# cyrf6936-bob.net
KiCad netlist of a schematic drawn in EAGLE
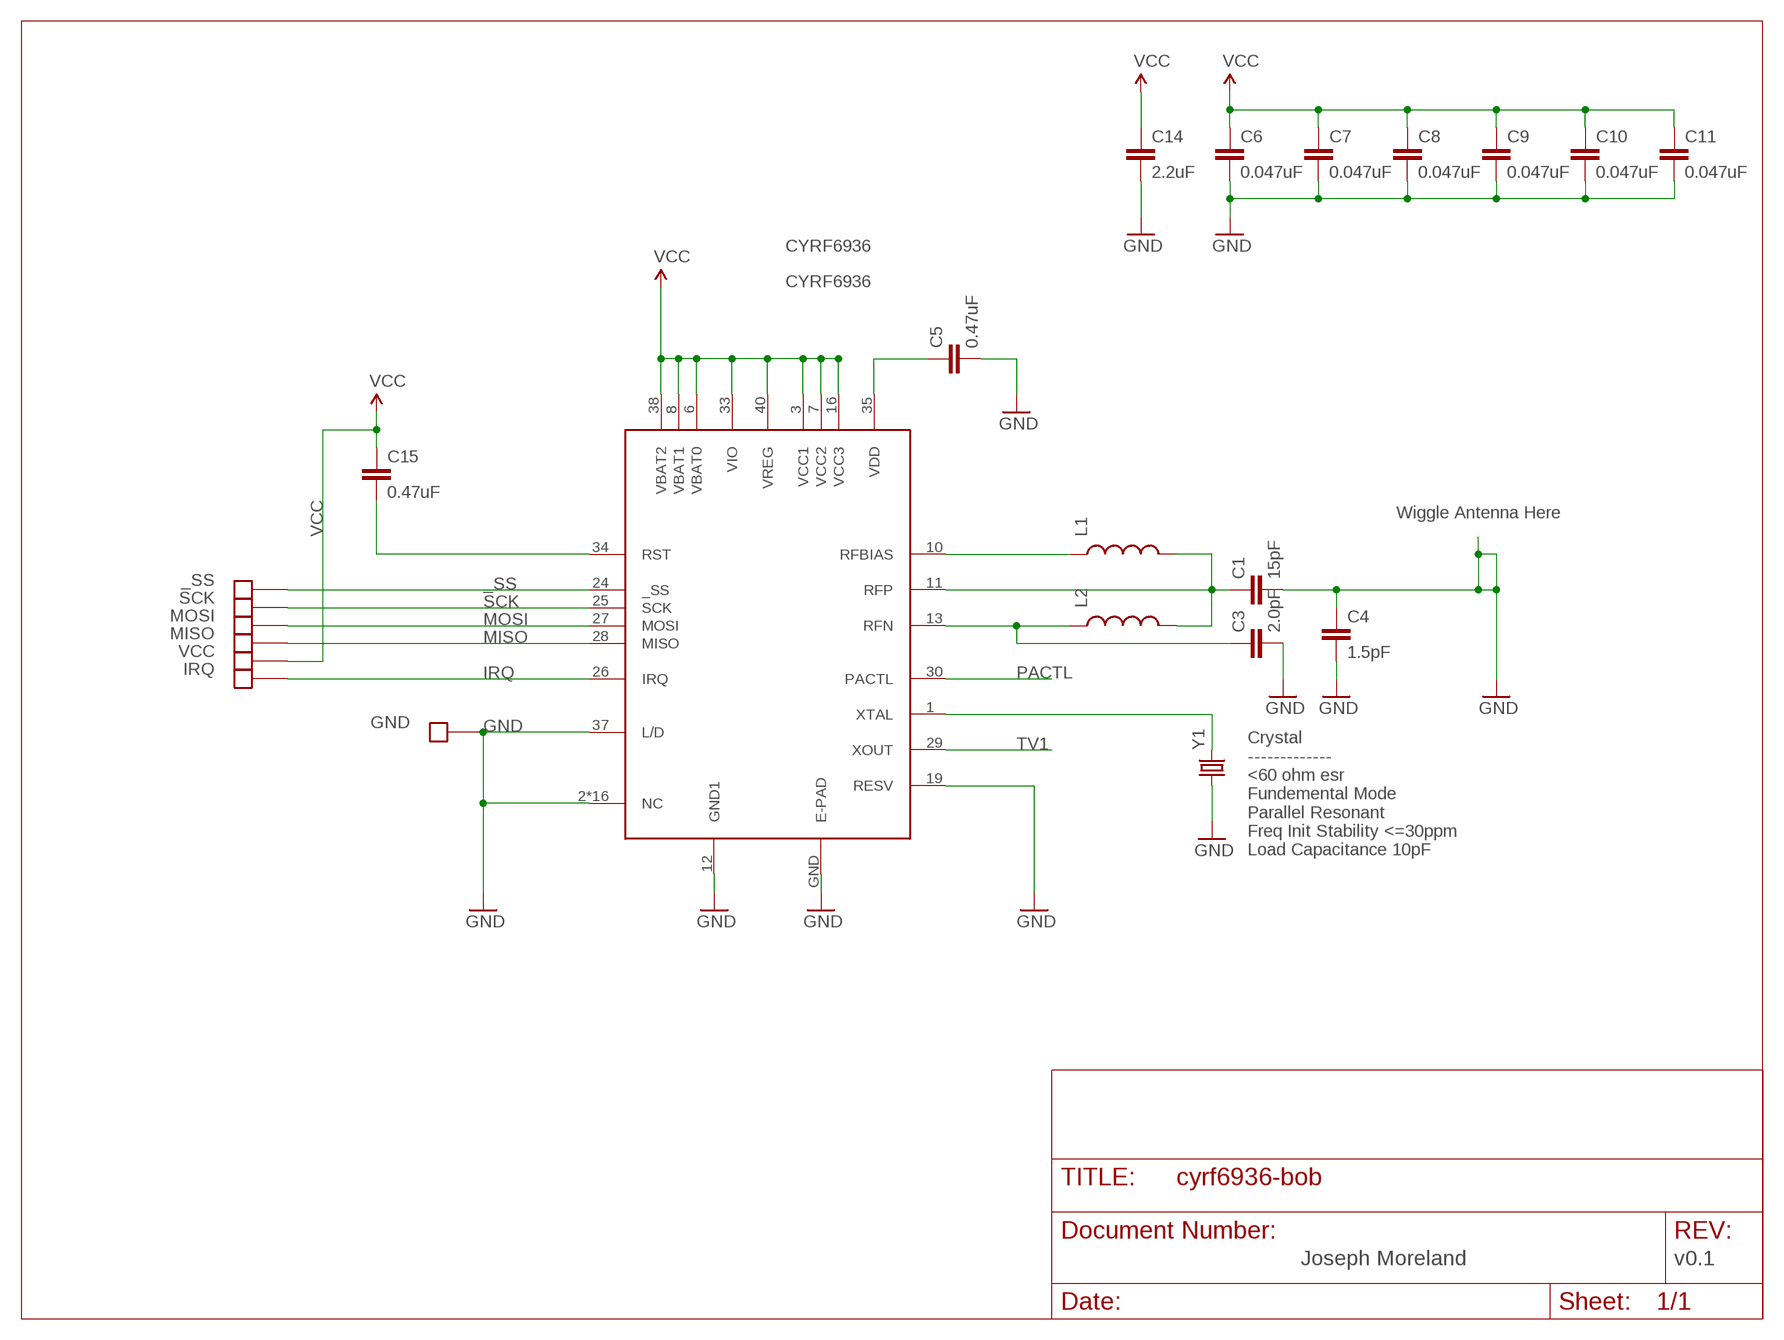
[diagram p0: schematic, sheet 1]

(export (version "E")
  (design (tool "Eeschema 10.0.6"))
  (components
    (comp (ref "C1")
      (value "15pF")
      (footprint "eagle-import:0402-CAP")
      (fields (field (name "PARTNO") "C0402C150J5GACTU"))
      (libsource (lib "eagle-import") (part "CAP0402-CAP"))
    )
    (comp (ref "C3")
      (value "2.0pF")
      (footprint "eagle-import:0402-CAP")
      (fields (field (name "PARTNO") "C0402C209C5GACTU"))
      (libsource (lib "eagle-import") (part "CAP0402-CAP"))
    )
    (comp (ref "C4")
      (value "1.5pF")
      (footprint "eagle-import:0402-CAP")
      (fields (field (name "PARTNO") "C0402C159B5GACTU"))
      (libsource (lib "eagle-import") (part "CAP0402-CAP"))
    )
    (comp (ref "C5")
      (value "0.47uF")
      (footprint "eagle-import:0402-CAP")
      (fields (field (name "PARTNO") "GRM155R60J474KE19D"))
      (libsource (lib "eagle-import") (part "CAP0402-CAP"))
    )
    (comp (ref "C6")
      (value "0.047uF")
      (footprint "eagle-import:0402-CAP")
      (fields (field (name "PARTNO") "0402YD473KAT2A"))
      (libsource (lib "eagle-import") (part "CAP0402-CAP"))
    )
    (comp (ref "C7")
      (value "0.047uF")
      (footprint "eagle-import:0402-CAP")
      (fields (field (name "PARTNO") "0402YD473KAT2A"))
      (libsource (lib "eagle-import") (part "CAP0402-CAP"))
    )
    (comp (ref "C8")
      (value "0.047uF")
      (footprint "eagle-import:0402-CAP")
      (fields (field (name "PARTNO") "0402YD473KAT2A"))
      (libsource (lib "eagle-import") (part "CAP0402-CAP"))
    )
    (comp (ref "C9")
      (value "0.047uF")
      (footprint "eagle-import:0402-CAP")
      (fields (field (name "PARTNO") "0402YD473KAT2A"))
      (libsource (lib "eagle-import") (part "CAP0402-CAP"))
    )
    (comp (ref "C10")
      (value "0.047uF")
      (footprint "eagle-import:0402-CAP")
      (fields (field (name "PARTNO") "0402YD473KAT2A"))
      (libsource (lib "eagle-import") (part "CAP0402-CAP"))
    )
    (comp (ref "C11")
      (value "0.047uF")
      (footprint "eagle-import:0402-CAP")
      (fields (field (name "PARTNO") "0402YD473KAT2A"))
      (libsource (lib "eagle-import") (part "CAP0402-CAP"))
    )
    (comp (ref "C14")
      (value "2.2uF")
      (footprint "eagle-import:0805")
      (fields (field (name "PARTNO") "GRM21BR71A225KA01L"))
      (libsource (lib "eagle-import") (part "CAP0805"))
    )
    (comp (ref "C15")
      (value "0.47uF")
      (footprint "eagle-import:0402-CAP")
      (fields (field (name "PARTNO") "GRM155R60J474KE19D"))
      (libsource (lib "eagle-import") (part "CAP0402-CAP"))
    )
    (comp (ref "CYRF6936")
      (value "CYRF6936")
      (footprint "eagle-import:QFN40")
      (fields (field (name "PARTNO") "CYRF6936B-40LTXC"))
      (libsource (lib "eagle-import") (part "CYRF6936"))
    )
    (comp (ref "GND")
      (value "SOLDER_PAD")
      (footprint "eagle-import:SOLDER_PAD")
      (libsource (lib "eagle-import") (part "SOLDER_PAD"))
    )
    (comp (ref "IRQ")
      (value "SOLDER_PAD")
      (footprint "eagle-import:SOLDER_PAD")
      (libsource (lib "eagle-import") (part "SOLDER_PAD"))
    )
    (comp (ref "L1")
      (value "INDUCTOR0603")
      (footprint "eagle-import:0603")
      (fields (field (name "PARTNO") "ELJ-RE22NGFA"))
      (libsource (lib "eagle-import") (part "INDUCTOR0603"))
    )
    (comp (ref "L2")
      (value "INDUCTOR0402")
      (footprint "eagle-import:C0402")
      (fields (field (name "PARTNO") "ELJ-RF1N8DFB"))
      (libsource (lib "eagle-import") (part "INDUCTOR0402"))
    )
    (comp (ref "MISO")
      (value "SOLDER_PAD")
      (footprint "eagle-import:SOLDER_PAD")
      (libsource (lib "eagle-import") (part "SOLDER_PAD"))
    )
    (comp (ref "MOSI")
      (value "SOLDER_PAD")
      (footprint "eagle-import:SOLDER_PAD")
      (libsource (lib "eagle-import") (part "SOLDER_PAD"))
    )
    (comp (ref "SCK")
      (value "SOLDER_PAD")
      (footprint "eagle-import:SOLDER_PAD")
      (libsource (lib "eagle-import") (part "SOLDER_PAD"))
    )
    (comp (ref "VCC")
      (value "SOLDER_PAD")
      (footprint "eagle-import:SOLDER_PAD")
      (libsource (lib "eagle-import") (part "SOLDER_PAD"))
    )
    (comp (ref "Y1")
      (value "CRYSTAL5X3")
      (footprint "eagle-import:CRYSTAL-SMD-5X3")
      (fields (field (name "PARTNO") "7B-12.000MEEQ-T"))
      (libsource (lib "eagle-import") (part "CRYSTAL5X3"))
    )
    (comp (ref "_SS")
      (value "SOLDER_PAD")
      (footprint "eagle-import:SOLDER_PAD")
      (libsource (lib "eagle-import") (part "SOLDER_PAD"))
    )
  )
  (nets
    (net (code "1") (name "/IRQ") (class "Default")
      (node (ref "CYRF6936") (pin "26") (pinfunction "IRQ_26") (pintype "bidirectional"))
      (node (ref "IRQ") (pin "SPAD") (pinfunction "NET_SPAD") (pintype "bidirectional"))
    )
    (net (code "2") (name "/MISO") (class "Default")
      (node (ref "CYRF6936") (pin "28") (pinfunction "MISO_28") (pintype "bidirectional"))
      (node (ref "MISO") (pin "SPAD") (pinfunction "NET_SPAD") (pintype "bidirectional"))
    )
    (net (code "3") (name "/MOSI") (class "Default")
      (node (ref "CYRF6936") (pin "27") (pinfunction "MOSI_27") (pintype "bidirectional"))
      (node (ref "MOSI") (pin "SPAD") (pinfunction "NET_SPAD") (pintype "bidirectional"))
    )
    (net (code "4") (name "/PACTL") (class "Default")
      (node (ref "CYRF6936") (pin "30") (pinfunction "PACTL_30") (pintype "bidirectional"))
    )
    (net (code "5") (name "/SCK") (class "Default")
      (node (ref "CYRF6936") (pin "25") (pinfunction "SCK_25") (pintype "bidirectional"))
      (node (ref "SCK") (pin "SPAD") (pinfunction "NET_SPAD") (pintype "bidirectional"))
    )
    (net (code "6") (name "/TV1") (class "Default")
      (node (ref "CYRF6936") (pin "29") (pinfunction "XOUT_29") (pintype "bidirectional"))
    )
    (net (code "7") (name "/_SS") (class "Default")
      (node (ref "CYRF6936") (pin "24") (pinfunction "_SS_24") (pintype "bidirectional"))
      (node (ref "_SS") (pin "SPAD") (pinfunction "NET_SPAD") (pintype "bidirectional"))
    )
    (net (code "8") (name "GND") (class "Default")
      (node (ref "C1") (pin "2") (pinfunction "2_2") (pintype "passive"))
      (node (ref "C10") (pin "2") (pinfunction "2_2") (pintype "passive"))
      (node (ref "C11") (pin "2") (pinfunction "2_2") (pintype "passive"))
      (node (ref "C14") (pin "2") (pinfunction "2_2") (pintype "passive"))
      (node (ref "C3") (pin "2") (pinfunction "2_2") (pintype "passive"))
      (node (ref "C4") (pin "1") (pinfunction "1_1") (pintype "passive"))
      (node (ref "C4") (pin "2") (pinfunction "2_2") (pintype "passive"))
      (node (ref "C5") (pin "2") (pinfunction "2_2") (pintype "passive"))
      (node (ref "C6") (pin "2") (pinfunction "2_2") (pintype "passive"))
      (node (ref "C7") (pin "2") (pinfunction "2_2") (pintype "passive"))
      (node (ref "C8") (pin "2") (pinfunction "2_2") (pintype "passive"))
      (node (ref "C9") (pin "2") (pinfunction "2_2") (pintype "passive"))
      (node (ref "CYRF6936") (pin "12") (pinfunction "GND1_12") (pintype "bidirectional"))
      (node (ref "CYRF6936") (pin "14") (pinfunction "NC_14") (pintype "bidirectional"))
      (node (ref "CYRF6936") (pin "15") (pinfunction "NC_15") (pintype "bidirectional"))
      (node (ref "CYRF6936") (pin "17") (pinfunction "NC_17") (pintype "bidirectional"))
      (node (ref "CYRF6936") (pin "18") (pinfunction "NC_18") (pintype "bidirectional"))
      (node (ref "CYRF6936") (pin "19") (pinfunction "RESV_19") (pintype "bidirectional"))
      (node (ref "CYRF6936") (pin "2") (pinfunction "NC_2") (pintype "bidirectional"))
      (node (ref "CYRF6936") (pin "20") (pinfunction "NC_20") (pintype "bidirectional"))
      (node (ref "CYRF6936") (pin "21") (pinfunction "NC_21") (pintype "bidirectional"))
      (node (ref "CYRF6936") (pin "22") (pinfunction "NC_22") (pintype "bidirectional"))
      (node (ref "CYRF6936") (pin "23") (pinfunction "NC_23") (pintype "bidirectional"))
      (node (ref "CYRF6936") (pin "31") (pinfunction "NC_31") (pintype "bidirectional"))
      (node (ref "CYRF6936") (pin "32") (pinfunction "NC_32") (pintype "bidirectional"))
      (node (ref "CYRF6936") (pin "36") (pinfunction "NC_36") (pintype "bidirectional"))
      (node (ref "CYRF6936") (pin "37") (pinfunction "L/D_37") (pintype "bidirectional"))
      (node (ref "CYRF6936") (pin "39") (pinfunction "NC_39") (pintype "bidirectional"))
      (node (ref "CYRF6936") (pin "4") (pinfunction "NC_4") (pintype "bidirectional"))
      (node (ref "CYRF6936") (pin "5") (pinfunction "NC_5") (pintype "bidirectional"))
      (node (ref "CYRF6936") (pin "9") (pinfunction "NC_9") (pintype "bidirectional"))
      (node (ref "CYRF6936") (pin "GND") (pinfunction "E-PAD_GND") (pintype "bidirectional"))
      (node (ref "GND") (pin "SPAD") (pinfunction "NET_SPAD") (pintype "bidirectional"))
      (node (ref "Y1") (pin "1") (pinfunction "1_1") (pintype "passive"))
    )
    (net (code "9") (name "Net-(CYRF6936-RFBIAS)") (class "Default")
      (node (ref "CYRF6936") (pin "10") (pinfunction "RFBIAS_10") (pintype "bidirectional"))
      (node (ref "L1") (pin "1") (pinfunction "1_1") (pintype "passive"))
    )
    (net (code "10") (name "Net-(CYRF6936-RFN)") (class "Default")
      (node (ref "C3") (pin "1") (pinfunction "1_1") (pintype "passive"))
      (node (ref "CYRF6936") (pin "13") (pinfunction "RFN_13") (pintype "bidirectional"))
      (node (ref "L2") (pin "1") (pinfunction "1_1") (pintype "passive"))
    )
    (net (code "11") (name "Net-(CYRF6936-RFP)") (class "Default")
      (node (ref "C1") (pin "1") (pinfunction "1_1") (pintype "passive"))
      (node (ref "CYRF6936") (pin "11") (pinfunction "RFP_11") (pintype "bidirectional"))
      (node (ref "L1") (pin "2") (pinfunction "2_2") (pintype "passive"))
      (node (ref "L2") (pin "2") (pinfunction "2_2") (pintype "passive"))
    )
    (net (code "12") (name "Net-(CYRF6936-RST)") (class "Default")
      (node (ref "C15") (pin "2") (pinfunction "2_2") (pintype "passive"))
      (node (ref "CYRF6936") (pin "34") (pinfunction "RST_34") (pintype "bidirectional"))
    )
    (net (code "13") (name "Net-(CYRF6936-VDD)") (class "Default")
      (node (ref "C5") (pin "1") (pinfunction "1_1") (pintype "passive"))
      (node (ref "CYRF6936") (pin "35") (pinfunction "VDD_35") (pintype "bidirectional"))
    )
    (net (code "14") (name "Net-(CYRF6936-XTAL)") (class "Default")
      (node (ref "CYRF6936") (pin "1") (pinfunction "XTAL_1") (pintype "bidirectional"))
      (node (ref "Y1") (pin "3") (pinfunction "2_3") (pintype "passive"))
    )
    (net (code "15") (name "VCC") (class "Default")
      (node (ref "C10") (pin "1") (pinfunction "1_1") (pintype "passive"))
      (node (ref "C11") (pin "1") (pinfunction "1_1") (pintype "passive"))
      (node (ref "C14") (pin "1") (pinfunction "1_1") (pintype "passive"))
      (node (ref "C15") (pin "1") (pinfunction "1_1") (pintype "passive"))
      (node (ref "C6") (pin "1") (pinfunction "1_1") (pintype "passive"))
      (node (ref "C7") (pin "1") (pinfunction "1_1") (pintype "passive"))
      (node (ref "C8") (pin "1") (pinfunction "1_1") (pintype "passive"))
      (node (ref "C9") (pin "1") (pinfunction "1_1") (pintype "passive"))
      (node (ref "CYRF6936") (pin "16") (pinfunction "VCC3_16") (pintype "bidirectional"))
      (node (ref "CYRF6936") (pin "3") (pinfunction "VCC1_3") (pintype "bidirectional"))
      (node (ref "CYRF6936") (pin "33") (pinfunction "VIO_33") (pintype "bidirectional"))
      (node (ref "CYRF6936") (pin "38") (pinfunction "VBAT2_38") (pintype "bidirectional"))
      (node (ref "CYRF6936") (pin "40") (pinfunction "VREG_40") (pintype "bidirectional"))
      (node (ref "CYRF6936") (pin "6") (pinfunction "VBAT0_6") (pintype "bidirectional"))
      (node (ref "CYRF6936") (pin "7") (pinfunction "VCC2_7") (pintype "bidirectional"))
      (node (ref "CYRF6936") (pin "8") (pinfunction "VBAT1_8") (pintype "bidirectional"))
      (node (ref "VCC") (pin "SPAD") (pinfunction "NET_SPAD") (pintype "bidirectional"))
    )
  )
)
